# GANDHVEDH_Ammonia.net
KiCad netlist of a schematic drawn in Altium Designer
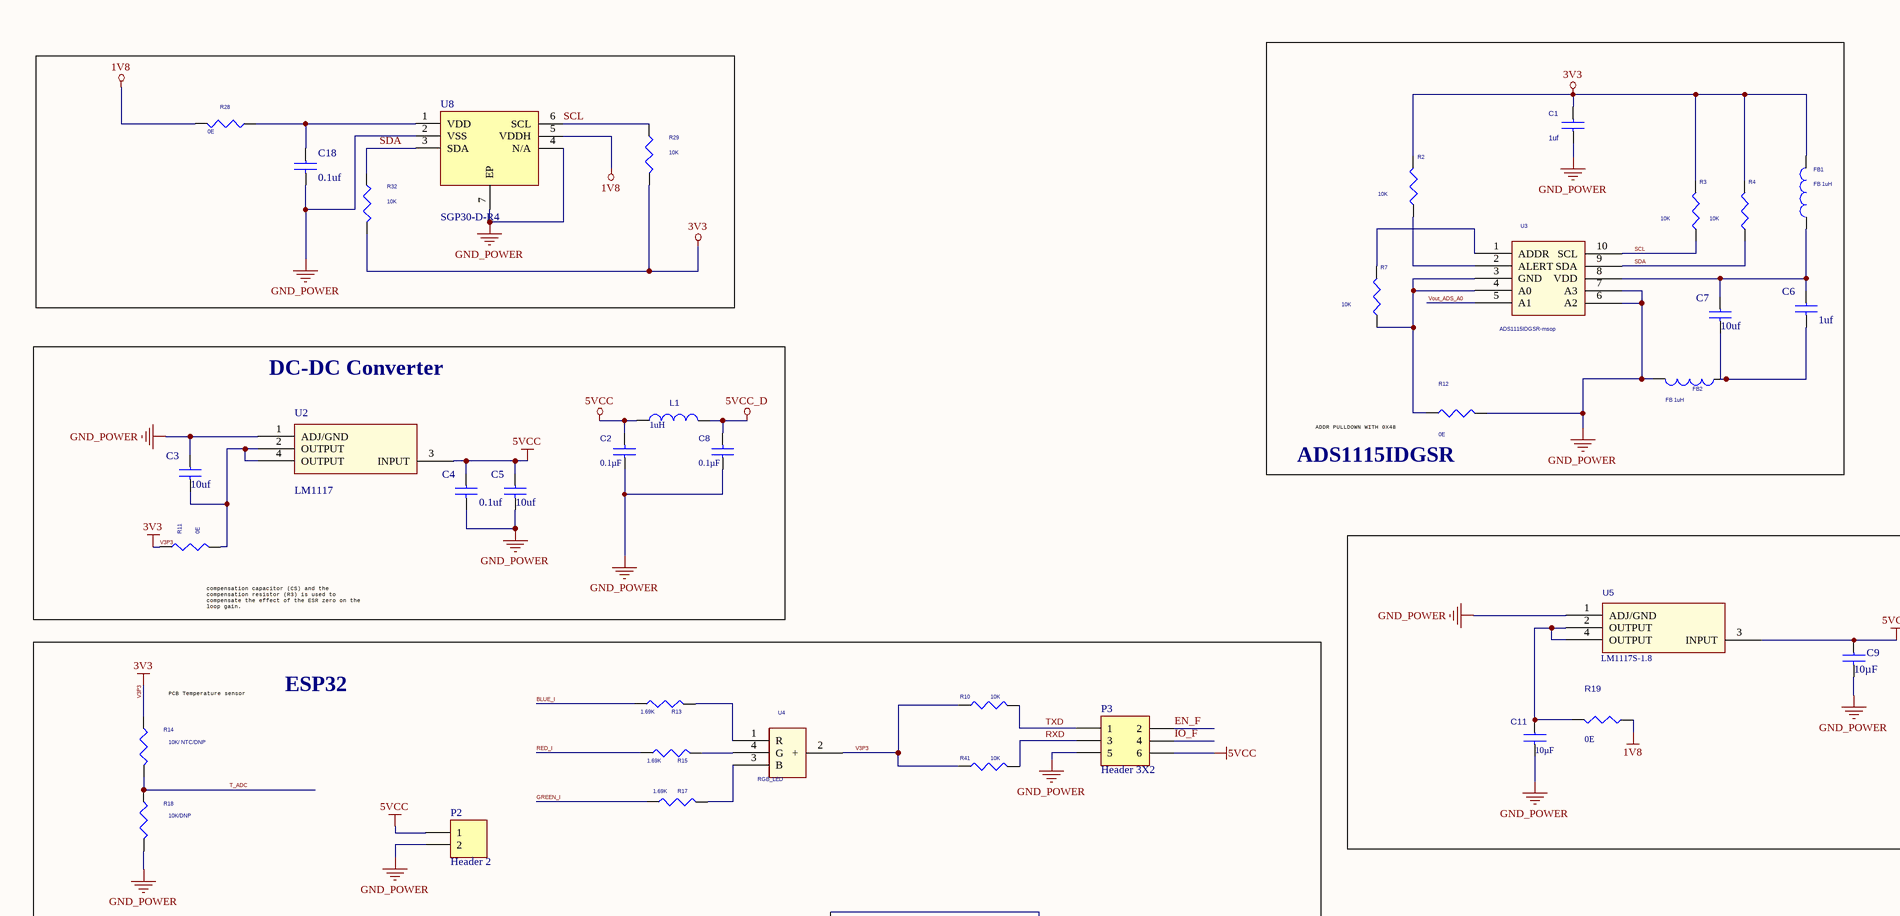
[diagram p0: GANDHVEDH_Ammonia.SchDoc, top left]
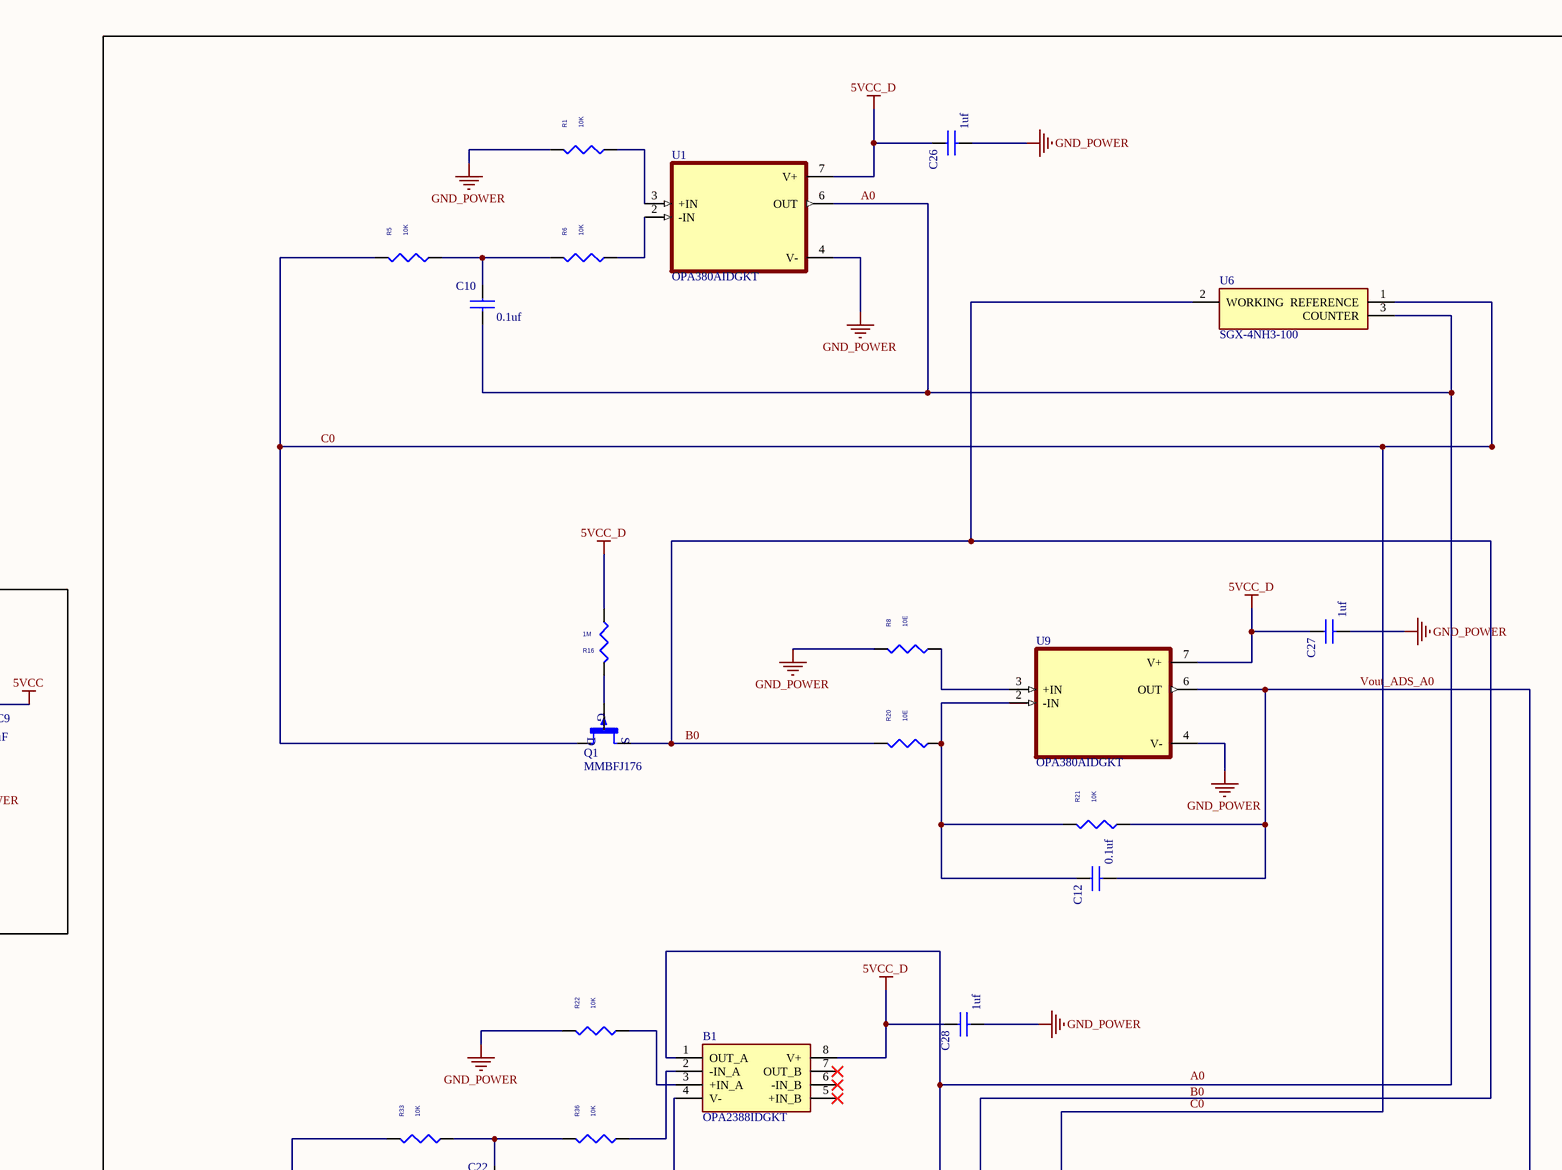
[diagram p1: GANDHVEDH_Ammonia.SchDoc, top right]
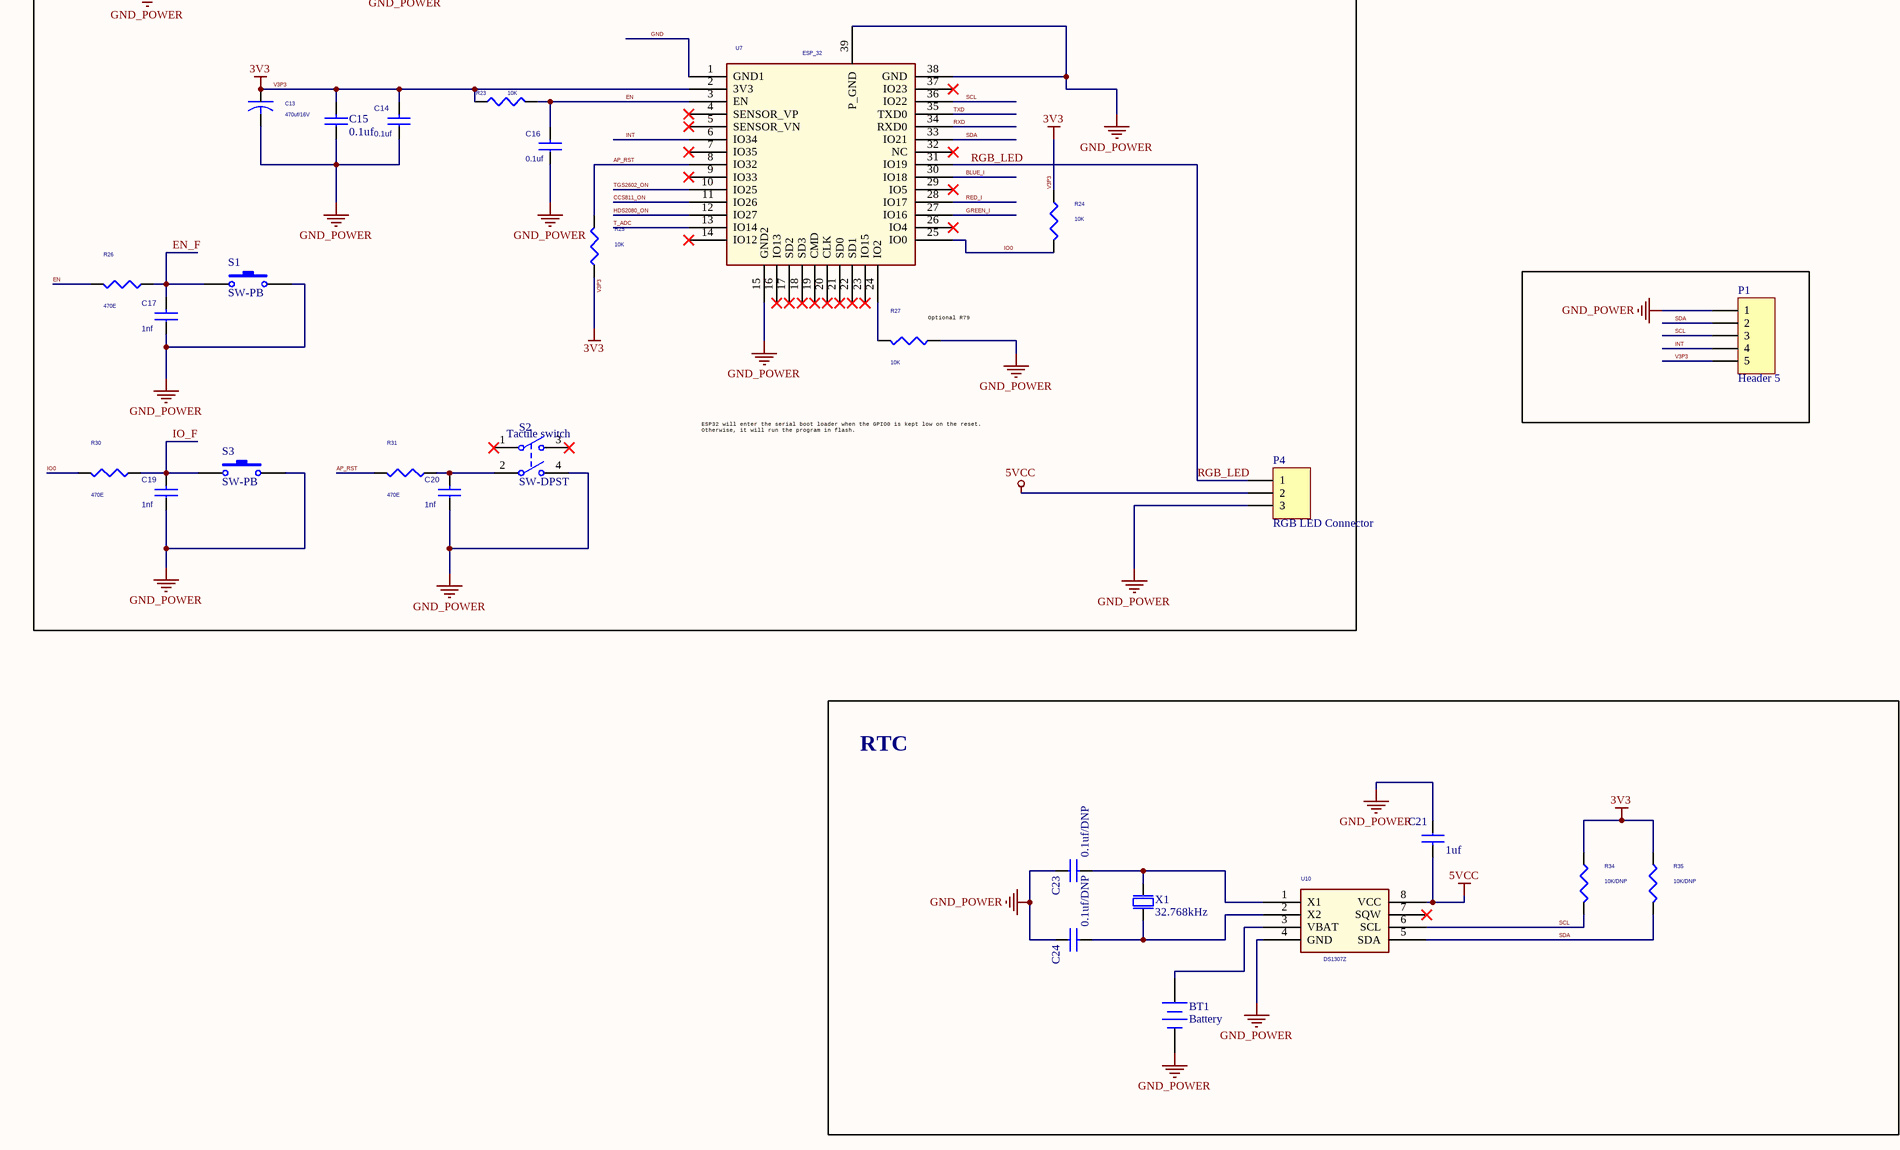
[diagram p2: GANDHVEDH_Ammonia.SchDoc, bottom left]
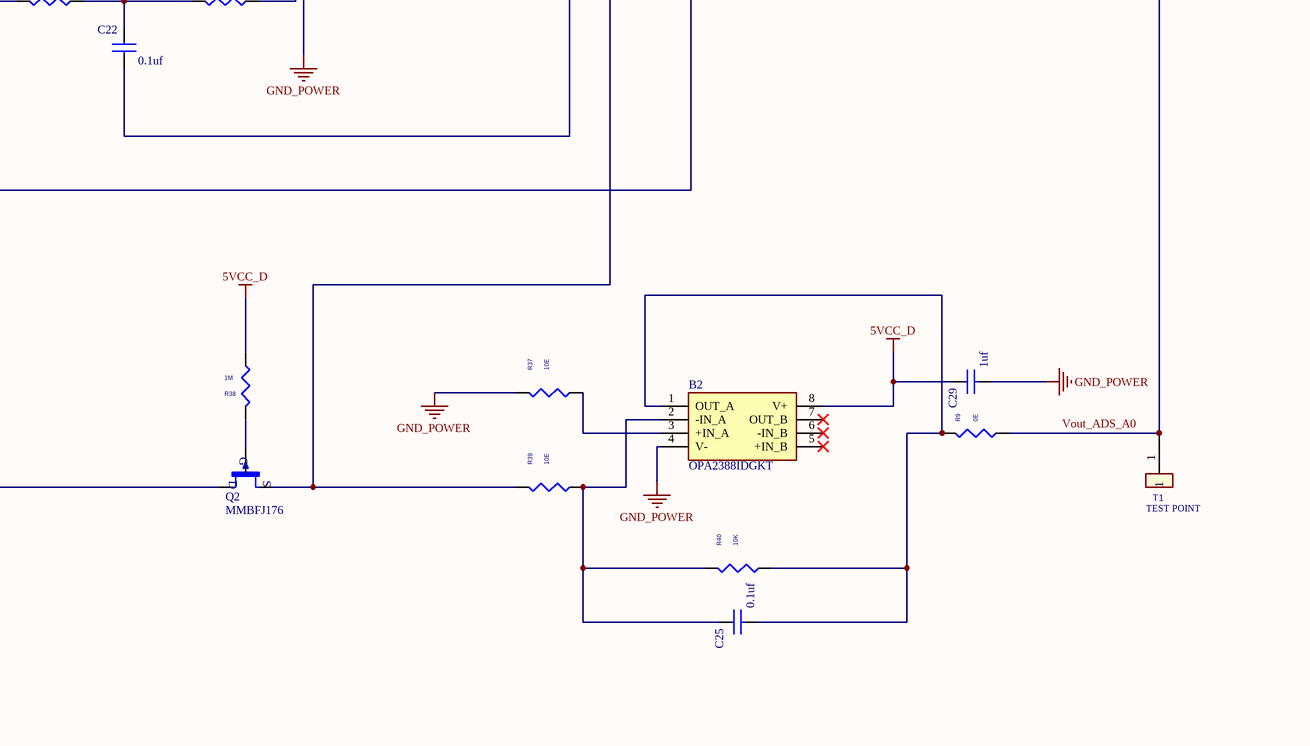
[diagram p3: GANDHVEDH_Ammonia.SchDoc, bottom right]

(export (version "E")
  (design (tool "Eeschema 10.0.6"))
  (components
    (comp (ref "B1")
      (value "OPA2388IDGKT")
      (footprint "SOP65P490X110-8N")
      (description "10MHz, CMOS, Zero-Drift, Zero-Crossover, True RRIO Precision Operational Amplifier")
      (fields (field (name "MOUSER PART NUMBER") "595-OPA2388IDGKT"))
      (libsource (lib "OPA2388IDGKT") (part "OPA2388IDGKT"))
    )
    (comp (ref "B2")
      (value "OPA2388IDGKT")
      (footprint "SOP65P490X110-8N")
      (description "10MHz, CMOS, Zero-Drift, Zero-Crossover, True RRIO Precision Operational Amplifier")
      (fields (field (name "MOUSER PART NUMBER") "595-OPA2388IDGKT"))
      (libsource (lib "OPA2388IDGKT") (part "OPA2388IDGKT"))
    )
    (comp (ref "BT1")
      (value "Battery")
      (footprint "Sensor Card:MPD_BK-912-TR")
      (description "Multicell Battery")
      (fields (field (name "PUBLISHER") "Altium Limited"))
      (libsource (lib "Miscellaneous Devices") (part "Battery"))
    )
    (comp (ref "C1")
      (value "1uf")
      (footprint "C0603")
      (description "CAP CER SMD 0.1µF/16V")
      (fields
        (field (name "MANUFACTURER") "Murata Electronics North America")
        (field (name "MANUFACTURER PART NUMBER") "GRM155R61H104KE19D")
      )
      (libsource (lib "Passive Component") (part "CAP_C_0.1µF/16V"))
    )
    (comp (ref "C2")
      (value "0.1µF")
      (footprint "C0603")
      (description "CAP CER SMD 0.1µF/16V")
      (fields
        (field (name "MANUFACTURER") "Murata Electronics North America")
        (field (name "MANUFACTURER PART NUMBER") "GRM155R61H104KE19D")
      )
      (libsource (lib "Passive Component") (part "CAP_C_0.1µF/16V"))
    )
    (comp (ref "C3")
      (value "10uf")
      (footprint "C0603")
      (description "CAP CER SMD 10µF/35V")
      (fields
        (field (name "MANUFACTURER") "Taiyo Yuden")
        (field (name "MANUFACTURER PART NUMBER") "GMK316AB7106KL-TR")
      )
      (libsource (lib "Passive Component") (part "CAP_C_10µF/35V"))
    )
    (comp (ref "C4")
      (value "0.1uf")
      (footprint "C0603")
      (description "CAP CER SMD 0.1µF/50V")
      (fields
        (field (name "MANUFACTURER") "Yageo")
        (field (name "MANUFACTURER PART NUMBER") "CC0805ZRY5V9BB104")
      )
      (libsource (lib "Passive Component") (part "CAP_C_0.1µF/50V"))
    )
    (comp (ref "C5")
      (value "10uf")
      (footprint "C0603")
      (description "CAP CER SMD 10µF/35V")
      (fields
        (field (name "MANUFACTURER") "Taiyo Yuden")
        (field (name "MANUFACTURER PART NUMBER") "GMK316AB7106KL-TR")
      )
      (libsource (lib "Passive Component") (part "CAP_C_10µF/35V"))
    )
    (comp (ref "C6")
      (value "1uf")
      (footprint "C0603")
      (description "CAP CER SMD 0.1µF/50V")
      (fields
        (field (name "MANUFACTURER") "Yageo")
        (field (name "MANUFACTURER PART NUMBER") "CC0805ZRY5V9BB104")
      )
      (libsource (lib "Passive Component") (part "CAP_C_0.1µF/50V"))
    )
    (comp (ref "C7")
      (value "10uf")
      (footprint "C0603")
      (description "CAP CER SMD 10µF/35V")
      (fields
        (field (name "MANUFACTURER") "Taiyo Yuden")
        (field (name "MANUFACTURER PART NUMBER") "GMK316AB7106KL-TR")
      )
      (libsource (lib "Passive Component") (part "CAP_C_10µF/35V"))
    )
    (comp (ref "C8")
      (value "0.1µF")
      (footprint "C0603")
      (description "CAP CER SMD 0.1µF/16V")
      (fields
        (field (name "MANUFACTURER") "Murata Electronics North America")
        (field (name "MANUFACTURER PART NUMBER") "GRM155R61H104KE19D")
      )
      (libsource (lib "Passive Component") (part "CAP_C_0.1µF/16V"))
    )
    (comp (ref "C9")
      (value "10µF")
      (footprint "R0603")
      (description "CAP CER SMD 10µF/35V")
      (fields
        (field (name "MANUFACTURER") "Taiyo Yuden")
        (field (name "MANUFACTURER PART NUMBER") "GMK316AB7106KL-TR")
      )
      (libsource (lib "Passive Component") (part "CAP_C_10µF/35V"))
    )
    (comp (ref "C10")
      (value "0.1uf")
      (footprint "C0603")
      (description "CAP CER SMD 0.1µF/50V")
      (fields
        (field (name "MANUFACTURER") "Yageo")
        (field (name "MANUFACTURER PART NUMBER") "CC0805ZRY5V9BB104")
      )
      (libsource (lib "Passive Component") (part "CAP_C_0.1µF/50V"))
    )
    (comp (ref "C11")
      (value "10µF")
      (footprint "C0603")
      (description "CAP CER SMD 10µF/35V")
      (fields
        (field (name "MANUFACTURER") "Taiyo Yuden")
        (field (name "MANUFACTURER PART NUMBER") "GMK316AB7106KL-TR")
      )
      (libsource (lib "Passive Component") (part "CAP_C_10µF/35V"))
    )
    (comp (ref "C12")
      (value "0.1uf")
      (footprint "C0603")
      (description "CAP CER SMD 0.1µF/50V")
      (fields
        (field (name "MANUFACTURER") "Yageo")
        (field (name "MANUFACTURER PART NUMBER") "CC0805ZRY5V9BB104")
      )
      (libsource (lib "Passive Component") (part "CAP_C_0.1µF/50V"))
    )
    (comp (ref "C13")
      (value "470uf/16V")
      (footprint "C16, C49, C58")
      (description "CAP ALUM 470UF 20% 50V RADIAL")
      (fields (field (name "PART NUMBER") "871-B41896E6477M000"))
      (libsource (lib "*") (part "CAP"))
    )
    (comp (ref "C14")
      (value "0.1uf")
      (footprint "C0603")
      (description "CAP CER SMD 0.1µF/16V")
      (fields
        (field (name "MANUFACTURER") "Murata Electronics North America")
        (field (name "MANUFACTURER PART NUMBER") "GRM155R61H104KE19D")
      )
      (libsource (lib "Passive Component") (part "CAP_C_0.1µF/16V"))
    )
    (comp (ref "C15")
      (value "0.1uf")
      (footprint "C0603")
      (description "CAP CER SMD 10µF/10V")
      (fields
        (field (name "MANUFACTURER") "Yageo")
        (field (name "MANUFACTURER PART NUMBER") "CC0805ZKY5V6BB106")
      )
      (libsource (lib "Passive Component") (part "CAP_C_10µF/10V"))
    )
    (comp (ref "C16")
      (value "0.1uf")
      (footprint "C0603")
      (description "CAP CER SMD 0.1µF/16V")
      (fields
        (field (name "MANUFACTURER") "Murata Electronics North America")
        (field (name "MANUFACTURER PART NUMBER") "GRM155R61H104KE19D")
      )
      (libsource (lib "Passive Component") (part "CAP_C_0.1µF/16V"))
    )
    (comp (ref "C17")
      (value "1nf")
      (footprint "C0603")
      (description "CAP CER SMD 0.1µF/16V")
      (fields
        (field (name "MANUFACTURER") "Murata Electronics North America")
        (field (name "MANUFACTURER PART NUMBER") "GRM155R61H104KE19D")
      )
      (libsource (lib "Passive Component") (part "CAP_C_0.1µF/16V"))
    )
    (comp (ref "C18")
      (value "0.1uf")
      (footprint "C0603")
      (description "CAP CER SMD 0.1µF/50V")
      (fields
        (field (name "MANUFACTURER") "Yageo")
        (field (name "MANUFACTURER PART NUMBER") "CC0805ZRY5V9BB104")
      )
      (libsource (lib "Passive Component") (part "CAP_C_0.1µF/50V"))
    )
    (comp (ref "C19")
      (value "1nf")
      (footprint "C0603")
      (description "CAP CER SMD 0.1µF/16V")
      (fields
        (field (name "MANUFACTURER") "Murata Electronics North America")
        (field (name "MANUFACTURER PART NUMBER") "GRM155R61H104KE19D")
      )
      (libsource (lib "Passive Component") (part "CAP_C_0.1µF/16V"))
    )
    (comp (ref "C20")
      (value "1nf")
      (footprint "C0603")
      (description "CAP CER SMD 0.1µF/16V")
      (fields
        (field (name "MANUFACTURER") "Murata Electronics North America")
        (field (name "MANUFACTURER PART NUMBER") "GRM155R61H104KE19D")
      )
      (libsource (lib "Passive Component") (part "CAP_C_0.1µF/16V"))
    )
    (comp (ref "C21")
      (value "1uf")
      (footprint "C0603")
      (description "CAP CER SMD 0.1µF/50V")
      (fields
        (field (name "MANUFACTURER") "Yageo")
        (field (name "MANUFACTURER PART NUMBER") "CC0805ZRY5V9BB104")
      )
      (libsource (lib "Passive Component") (part "CAP_C_0.1µF/50V"))
    )
    (comp (ref "C22")
      (value "0.1uf")
      (footprint "C0603")
      (description "CAP CER SMD 0.1µF/50V")
      (fields
        (field (name "MANUFACTURER") "Yageo")
        (field (name "MANUFACTURER PART NUMBER") "CC0805ZRY5V9BB104")
      )
      (libsource (lib "Passive Component") (part "CAP_C_0.1µF/50V"))
    )
    (comp (ref "C23")
      (value "0.1uf/DNP")
      (footprint "C0603")
      (description "CAP CER SMD 0.1µF/50V")
      (fields
        (field (name "MANUFACTURER") "Yageo")
        (field (name "MANUFACTURER PART NUMBER") "CC0805ZRY5V9BB104")
      )
      (libsource (lib "Passive Component") (part "CAP_C_0.1µF/50V"))
    )
    (comp (ref "C24")
      (value "0.1uf/DNP")
      (footprint "C0603")
      (description "CAP CER SMD 0.1µF/50V")
      (fields
        (field (name "MANUFACTURER") "Yageo")
        (field (name "MANUFACTURER PART NUMBER") "CC0805ZRY5V9BB104")
      )
      (libsource (lib "Passive Component") (part "CAP_C_0.1µF/50V"))
    )
    (comp (ref "C25")
      (value "0.1uf")
      (footprint "C0603")
      (description "CAP CER SMD 0.1µF/50V")
      (fields
        (field (name "MANUFACTURER") "Yageo")
        (field (name "MANUFACTURER PART NUMBER") "CC0805ZRY5V9BB104")
      )
      (libsource (lib "Passive Component") (part "CAP_C_0.1µF/50V"))
    )
    (comp (ref "C26")
      (value "1uf")
      (footprint "C0603")
      (description "CAP CER SMD 0.1µF/50V")
      (fields
        (field (name "MANUFACTURER") "Yageo")
        (field (name "MANUFACTURER PART NUMBER") "CC0805ZRY5V9BB104")
      )
      (libsource (lib "Passive Component") (part "CAP_C_0.1µF/50V"))
    )
    (comp (ref "C27")
      (value "1uf")
      (footprint "C0603")
      (description "CAP CER SMD 0.1µF/50V")
      (fields
        (field (name "MANUFACTURER") "Yageo")
        (field (name "MANUFACTURER PART NUMBER") "CC0805ZRY5V9BB104")
      )
      (libsource (lib "Passive Component") (part "CAP_C_0.1µF/50V"))
    )
    (comp (ref "C28")
      (value "1uf")
      (footprint "C0603")
      (description "CAP CER SMD 0.1µF/50V")
      (fields
        (field (name "MANUFACTURER") "Yageo")
        (field (name "MANUFACTURER PART NUMBER") "CC0805ZRY5V9BB104")
      )
      (libsource (lib "Passive Component") (part "CAP_C_0.1µF/50V"))
    )
    (comp (ref "C29")
      (value "1uf")
      (footprint "C0603")
      (description "CAP CER SMD 0.1µF/50V")
      (fields
        (field (name "MANUFACTURER") "Yageo")
        (field (name "MANUFACTURER PART NUMBER") "CC0805ZRY5V9BB104")
      )
      (libsource (lib "Passive Component") (part "CAP_C_0.1µF/50V"))
    )
    (comp (ref "FB1")
      (value "FB 1uH")
      (footprint "C0603")
      (description "FILTER CHIP 120 OHM 3A 0603")
      (fields (field (name "MANUFACTURER PART NUMBER") "MMZ2012Y152B"))
      (libsource (lib "*") (part "INDUCTOR"))
    )
    (comp (ref "FB2")
      (value "FB 1uH")
      (footprint "C0603")
      (description "FILTER CHIP 120 OHM 3A 0603")
      (fields (field (name "DISTRIBUTOR PART NUMBER") "MMZ2012Y152B"))
      (libsource (lib "*") (part "INDUCTOR"))
    )
    (comp (ref "L1")
      (value "1uH")
      (footprint "L3, L4, L5, L6, L7")
      (description "FERRITE BEAD 120 OHM 0603 1LN")
      (fields (field (name "PART NUMBER") "490-3996-1-ND"))
      (libsource (lib "*") (part "INDUCTOR"))
    )
    (comp (ref "P1")
      (value "Header 5")
      (footprint "J2")
      (description "Header, 5-Pin")
      (fields (field (name "PUBLISHER") "Altium Limited"))
      (libsource (lib "Miscellaneous Connectors") (part "Header 5"))
    )
    (comp (ref "P2")
      (value "Header 2")
      (footprint "Miscellaneous Connectors:HDR1X2")
      (description "Header, 2-Pin")
      (fields (field (name "PUBLISHER") "Altium Limited"))
      (libsource (lib "Miscellaneous Connectors") (part "Header 2"))
    )
    (comp (ref "P3")
      (value "Header 3X2")
      (footprint "P5 - new")
      (description "Header, 3-Pin, Dual row")
      (fields (field (name "PUBLISHER") "Altium Limited"))
      (libsource (lib "Miscellaneous Connectors") (part "Header 3X2"))
    )
    (comp (ref "P4")
      (value "RGB LED Connector")
      (footprint "P6")
      (description "Header, 3-Pin")
      (fields (field (name "PUBLISHER") "Altium Limited"))
      (libsource (lib "Miscellaneous Connectors") (part "Header 3"))
    )
    (comp (ref "Q1")
      (value "MMBFJ176")
      (footprint "SOT23")
      (description "JFET P-Channel 30V 225mW Surface Mount SOT-23-3")
      (fields (field (name "MF") "ON Semiconductor"))
      (libsource (lib "MMBFJ176") (part "MMBFJ176"))
    )
    (comp (ref "Q2")
      (value "MMBFJ176")
      (footprint "SOT23")
      (description "JFET P-Channel 30V 225mW Surface Mount SOT-23-3")
      (fields (field (name "MF") "ON Semiconductor"))
      (libsource (lib "MMBFJ176") (part "MMBFJ176"))
    )
    (comp (ref "R1") (value "10K") (footprint "R0603") (libsource (lib "*") (part "R")))
    (comp (ref "R2")
      (value "10K")
      (footprint "R0603")
      (description "RES SMD 4.7K OHM 1% 1/16W 0603")
      (fields (field (name "TOLERANCE") "1%") (field (name "DISTRIBUTOR PART NUMBER") "1276-3466-2-ND"))
      (libsource (lib "*") (part "R"))
    )
    (comp (ref "R3")
      (value "10K")
      (footprint "R0603")
      (description "RES SMD 4.7K OHM 1% 1/16W 0603")
      (fields (field (name "TOLERANCE") "1%") (field (name "DISTRIBUTOR PART NUMBER") "1276-3466-2-ND"))
      (libsource (lib "*") (part "R"))
    )
    (comp (ref "R4")
      (value "10K")
      (footprint "R0603")
      (description "RES SMD 4.7K OHM 1% 1/16W 0603")
      (fields (field (name "TOLERANCE") "1%") (field (name "DISTRIBUTOR PART NUMBER") "1276-3466-2-ND"))
      (libsource (lib "*") (part "R"))
    )
    (comp (ref "R5") (value "10K") (footprint "R0603") (libsource (lib "*") (part "R")))
    (comp (ref "R6") (value "10K") (footprint "R0603") (libsource (lib "*") (part "R")))
    (comp (ref "R7")
      (value "10K")
      (footprint "R0603")
      (description "RES SMD 4.7K OHM 1% 1/16W 0603")
      (fields (field (name "TOLERANCE") "1%") (field (name "DISTRIBUTOR PART NUMBER") "1276-3466-2-ND"))
      (libsource (lib "*") (part "R"))
    )
    (comp (ref "R8") (value "10E") (footprint "R0603") (libsource (lib "*") (part "R")))
    (comp (ref "R9") (value "0E") (footprint "R0603") (libsource (lib "*") (part "R")))
    (comp (ref "R10")
      (value "10K")
      (footprint "R_0603_W")
      (description "RES SMD 4.7K OHM 1% 1/16W 0603")
      (fields (field (name "PART NUMBER") "311-10KGRTR-ND"))
      (libsource (lib "*") (part "R"))
    )
    (comp (ref "R11")
      (value "0E")
      (footprint "R0603")
      (description "RES SMD 40.2K OHM 0.1% 1/5W 0603")
      (fields (field (name "PART NUMBER") "P20154TR-ND"))
      (libsource (lib "*") (part "R"))
    )
    (comp (ref "R12") (value "0E") (footprint "R0603") (libsource (lib "*") (part "R")))
    (comp (ref "R13")
      (value "1.69K")
      (footprint "R0603")
      (description "RES SMD 4.7K OHM 1% 1/16W 0603")
      (fields (field (name "PART NUMBER") "311-10KGRTR-ND"))
      (libsource (lib "*") (part "R"))
    )
    (comp (ref "R14")
      (value "10K/ NTC/DNP")
      (footprint "R0603")
      (description "THERMISTOR NTC 10KOHM 3380K 0603")
      (fields (field (name "PART NUMBER") "490-16279-2-ND"))
      (libsource (lib "*") (part "R"))
    )
    (comp (ref "R15")
      (value "1.69K")
      (footprint "R0603")
      (description "RES SMD 4.7K OHM 1% 1/16W 0603")
      (fields (field (name "PART NUMBER") "311-10KGRTR-ND"))
      (libsource (lib "*") (part "R"))
    )
    (comp (ref "R16") (value "1M") (footprint "R0603") (libsource (lib "*") (part "R")))
    (comp (ref "R17")
      (value "1.69K")
      (footprint "R0603")
      (description "RES SMD 4.7K OHM 1% 1/16W 0603")
      (fields (field (name "PART NUMBER") "311-10KGRTR-ND"))
      (libsource (lib "*") (part "R"))
    )
    (comp (ref "R18")
      (value "10K/DNP")
      (footprint "R0603")
      (description "RES SMD 4.7K OHM 1% 1/16W 0603")
      (fields (field (name "PART NUMBER") "311-10KGRTR-ND"))
      (libsource (lib "*") (part "R"))
    )
    (comp (ref "R19")
      (value "0E")
      (footprint "R0603")
      (description "RES SMD 470 OHM 1% 1/10W 0603")
      (fields (field (name "PART NUMBER") "311-470HRCT-ND"))
      (libsource (lib "*") (part "R"))
    )
    (comp (ref "R20") (value "10E") (footprint "R0603") (libsource (lib "*") (part "R")))
    (comp (ref "R21") (value "10K") (footprint "R0603") (libsource (lib "*") (part "R")))
    (comp (ref "R22") (value "10K") (footprint "R0603") (libsource (lib "*") (part "R")))
    (comp (ref "R23")
      (value "10K")
      (footprint "R0603")
      (description "RES SMD 4.7K OHM 1% 1/16W 0603")
      (fields (field (name "PART NUMBER") "311-10KGRTR-ND"))
      (libsource (lib "*") (part "R"))
    )
    (comp (ref "R24")
      (value "10K")
      (footprint "R0603")
      (description "RES SMD 4.7K OHM 1% 1/16W 0603")
      (fields (field (name "PART NUMBER") "311-10KGRTR-ND"))
      (libsource (lib "*") (part "R"))
    )
    (comp (ref "R25")
      (value "10K")
      (footprint "R0603")
      (description "RES SMD 4.7K OHM 1% 1/16W 0603")
      (fields (field (name "PART NUMBER") "311-10KGRTR-ND"))
      (libsource (lib "*") (part "R"))
    )
    (comp (ref "R26")
      (value "470E")
      (footprint "R0603")
      (description "RES SMD 470 OHM 1% 1/10W 0603")
      (fields (field (name "PART NUMBER") "311-470HRCT-ND"))
      (libsource (lib "*") (part "R"))
    )
    (comp (ref "R27")
      (value "10K")
      (footprint "R0603")
      (description "RES SMD 4.7K OHM 1% 1/16W 0603")
      (fields (field (name "PART NUMBER") "311-10KGRTR-ND"))
      (libsource (lib "*") (part "R"))
    )
    (comp (ref "R28")
      (value "0E")
      (footprint "R0603")
      (description "RES SMD 4.7K OHM 1% 1/16W 0603")
      (fields (field (name "PART NUMBER") "311-10KGRTR-ND"))
      (libsource (lib "*") (part "R"))
    )
    (comp (ref "R29")
      (value "10K")
      (footprint "R0603")
      (description "RES SMD 4.7K OHM 1% 1/16W 0603")
      (fields (field (name "PART NUMBER") "311-10KGRTR-ND"))
      (libsource (lib "*") (part "R"))
    )
    (comp (ref "R30")
      (value "470E")
      (footprint "R0603")
      (description "RES SMD 470 OHM 1% 1/10W 0603")
      (fields (field (name "PART NUMBER") "311-470HRCT-ND"))
      (libsource (lib "*") (part "R"))
    )
    (comp (ref "R31")
      (value "470E")
      (footprint "R0603")
      (description "RES SMD 470 OHM 1% 1/10W 0603")
      (fields (field (name "PART NUMBER") "311-470HRCT-ND"))
      (libsource (lib "*") (part "R"))
    )
    (comp (ref "R32")
      (value "10K")
      (footprint "R0603")
      (description "RES SMD 4.7K OHM 1% 1/16W 0603")
      (fields (field (name "PART NUMBER") "311-10KGRTR-ND"))
      (libsource (lib "*") (part "R"))
    )
    (comp (ref "R33") (value "10K") (footprint "R0603") (libsource (lib "*") (part "R")))
    (comp (ref "R34")
      (value "10K/DNP")
      (footprint "R0603")
      (description "RES SMD 4.7K OHM 1% 1/16W 0603")
      (fields (field (name "PART NUMBER") "311-10KGRTR-ND"))
      (libsource (lib "*") (part "R"))
    )
    (comp (ref "R35")
      (value "10K/DNP")
      (footprint "R0603")
      (description "RES SMD 4.7K OHM 1% 1/16W 0603")
      (fields (field (name "PART NUMBER") "311-10KGRTR-ND"))
      (libsource (lib "*") (part "R"))
    )
    (comp (ref "R36") (value "10K") (footprint "R0603") (libsource (lib "*") (part "R")))
    (comp (ref "R37") (value "10E") (footprint "R0603") (libsource (lib "*") (part "R")))
    (comp (ref "R38") (value "1M") (footprint "R0603") (libsource (lib "*") (part "R")))
    (comp (ref "R39") (value "10E") (footprint "R0603") (libsource (lib "*") (part "R")))
    (comp (ref "R40") (value "10K") (footprint "R0603") (libsource (lib "*") (part "R")))
    (comp (ref "R41")
      (value "10K")
      (footprint "R_0603_W")
      (description "RES SMD 4.7K OHM 1% 1/16W 0603")
      (fields (field (name "PART NUMBER") "311-10KGRTR-ND"))
      (libsource (lib "*") (part "R"))
    )
    (comp (ref "S1")
      (value "SW-PB")
      (footprint "*TE_FSMSM")
      (description "Switch")
      (fields (field (name "PUBLISHER") "Altium Limited"))
      (libsource (lib "Miscellaneous Devices") (part "SW-PB"))
    )
    (comp (ref "S2")
      (value "SW-DPST")
      (footprint "PCBComponent_1 - duplicate")
      (description "Double-Pole, Single-Throw Switch")
      (fields (field (name "PUBLISHER") "Altium Limited"))
      (libsource (lib "Miscellaneous Devices") (part "SW-DPST"))
    )
    (comp (ref "S3")
      (value "SW-PB")
      (footprint "*TE_FSMSM")
      (description "Switch")
      (fields (field (name "PUBLISHER") "Altium Limited"))
      (libsource (lib "Miscellaneous Devices") (part "SW-PB"))
    )
    (comp (ref "T1") (value "TEST POINT") (footprint "TP") (libsource (lib "*") (part "Test_P")))
    (comp (ref "U1")
      (value "OPA380AIDGKT")
      (footprint "SOP65P490X110-8N")
      (libsource (lib "OPA380AIDGKT") (part "OPA380AIDGKT"))
    )
    (comp (ref "U2")
      (value "LM1117")
      (footprint "U1, U24              SOT-223")
      (description "3.3V LDO")
      (fields (field (name "MANUFACTURER") "Texas Instruments"))
      (libsource (lib "PMIC") (part "TLV70033DDCT"))
    )
    (comp (ref "U3")
      (value "ADS1115IDGSR-msop")
      (footprint "U19, U20")
      (description "IC ADC 16BIT SIGMA-DELTA 10VSSOP")
      (fields (field (name "PART NUMBER") "595-ADS1115IDGST"))
      (libsource (lib "*") (part "ADS1115"))
    )
    (comp (ref "U4")
      (value "RGB_LED")
      (footprint "Sensor Card:WL-SFCW_1206")
      (fields (field (name "PART NUMBER") "754-1492-ND"))
      (libsource (lib "*") (part "RGB_LED_PTH_0"))
    )
    (comp (ref "U5")
      (value "LM1117S-1.8")
      (footprint "U1, U24              SOT-223")
      (description "3.3V LDO")
      (fields
        (field (name "MANUFACTURER") "Texas Instruments")
        (field (name "MANUFACTURER PART NUMBER") "LM1117")
      )
      (libsource (lib "PMIC") (part "TLV70033DDCT"))
    )
    (comp (ref "U6")
      (value "SGX-4NH3-100")
      (footprint "SGX4NH3100")
      (description "Air Quality Sensors 4 Series Ammonia sensor - 100ppm")
      (fields (field (name "MOUSER PART NUMBER") "523-SGX-4NH3-100"))
      (libsource (lib "SGX-4NH3-100") (part "SGX-4NH3-100"))
    )
    (comp (ref "U7")
      (value "ESP_32")
      (footprint "U20             ESP 32")
      (description "WIFI MODULE 128MBITS SPI FLASH")
      (fields (field (name "PART NUMBER") "356-ES32WROOM32D16MB"))
      (libsource (lib "*") (part "ESP32_SMD_1"))
    )
    (comp (ref "U8")
      (value "SGP30-D-R4")
      (footprint "SGP40-D-R4 (1):XCDR_SGP40-D-R4")
      (description "Integrated Circuit")
      (fields
        (field (name "MANUFACTURER_PART_NUMBER") "SGP40-D-R4")
        (field (name "MOUSER PART NUMBER") "403-SGP40-D-R4")
      )
      (libsource (lib "*") (part "SGP40-D-R4"))
    )
    (comp (ref "U9")
      (value "OPA380AIDGKT")
      (footprint "SOP65P490X110-8N")
      (libsource (lib "OPA380AIDGKT") (part "OPA380AIDGKT"))
    )
    (comp (ref "U10")
      (value "DS1307Z")
      (footprint "U14               SOIC-8N")
      (description "IC REG BUCK ADJUSTABLE 3A 8SOIC")
      (fields (field (name "PART NUMBER") "1589-1533-1-ND"))
      (libsource (lib "*") (part "MP1584_SOIC_0"))
    )
    (comp (ref "X1")
      (value "32.768kHz")
      (footprint "XTAL_ECS-.327-12.5-13FLX-C")
      (description "XTAL SMD 3215, 32.768kHz, Cl=9pF, Total Tol: ±50ppm")
      (fields
        (field (name "PART NUMBER") "XTAL_SMD3215_32.768kHz_9pF_General")
        (field (name "PUBLISHER") "Nordic Semiconductor")
      )
      (libsource (lib "Sensor Card") (part "XTAL_2-pin"))
    )
  )
  (nets
    (net (code "1") (name "/A0") (class "Default")
      (node (ref "B1") (pin "1") (pinfunction "OUT_A_1") (pintype "passive"))
      (node (ref "C10") (pin "2") (pinfunction "2_2") (pintype "passive"))
      (node (ref "C22") (pin "2") (pinfunction "2_2") (pintype "passive"))
      (node (ref "U1") (pin "6") (pinfunction "OUT_6") (pintype "output"))
      (node (ref "U6") (pin "3") (pinfunction "COUNTER_3") (pintype "passive"))
    )
    (net (code "2") (name "/AP_RST") (class "Default")
      (node (ref "R25") (pin "2") (pinfunction "2_2") (pintype "passive"))
      (node (ref "R31") (pin "2") (pinfunction "2_2") (pintype "passive"))
      (node (ref "U7") (pin "8") (pinfunction "IO32_8") (pintype "passive"))
    )
    (net (code "3") (name "/B0") (class "Default")
      (node (ref "Q1") (pin "2") (pinfunction "S_2") (pintype "passive"))
      (node (ref "Q2") (pin "2") (pinfunction "S_2") (pintype "passive"))
      (node (ref "R20") (pin "2") (pinfunction "2_2") (pintype "passive"))
      (node (ref "R39") (pin "2") (pinfunction "2_2") (pintype "passive"))
      (node (ref "U6") (pin "2") (pinfunction "WORKING_2") (pintype "passive"))
    )
    (net (code "4") (name "/BLUE_I") (class "Default")
      (node (ref "R13") (pin "1") (pinfunction "1_1") (pintype "passive"))
      (node (ref "U7") (pin "30") (pinfunction "IO18_30") (pintype "passive"))
    )
    (net (code "5") (name "/C0") (class "Default")
      (node (ref "Q1") (pin "1") (pinfunction "D_1") (pintype "passive"))
      (node (ref "Q2") (pin "1") (pinfunction "D_1") (pintype "passive"))
      (node (ref "R33") (pin "2") (pinfunction "2_2") (pintype "passive"))
      (node (ref "R5") (pin "2") (pinfunction "2_2") (pintype "passive"))
      (node (ref "U6") (pin "1") (pinfunction "REFERENCE_1") (pintype "passive"))
    )
    (net (code "6") (name "/CCS811_ON") (class "Default")
      (node (ref "U7") (pin "11") (pinfunction "IO26_11") (pintype "passive"))
    )
    (net (code "7") (name "/EN") (class "Default")
      (node (ref "C16") (pin "2") (pinfunction "2_2") (pintype "passive"))
      (node (ref "R23") (pin "2") (pinfunction "2_2") (pintype "passive"))
      (node (ref "R26") (pin "2") (pinfunction "2_2") (pintype "passive"))
      (node (ref "U7") (pin "3") (pinfunction "EN_3") (pintype "passive"))
    )
    (net (code "8") (name "/EN_F") (class "Default")
      (node (ref "C17") (pin "2") (pinfunction "2_2") (pintype "passive"))
      (node (ref "P3") (pin "2") (pinfunction "2_2") (pintype "passive"))
      (node (ref "R26") (pin "1") (pinfunction "1_1") (pintype "passive"))
      (node (ref "S1") (pin "1") (pinfunction "1_1") (pintype "passive"))
    )
    (net (code "9") (name "/GND") (class "Default")
      (node (ref "U7") (pin "1") (pinfunction "GND1_1") (pintype "passive"))
    )
    (net (code "10") (name "/GREEN_I") (class "Default")
      (node (ref "R17") (pin "1") (pinfunction "1_1") (pintype "passive"))
      (node (ref "U7") (pin "27") (pinfunction "IO16_27") (pintype "passive"))
    )
    (net (code "11") (name "/HDS2080_ON") (class "Default")
      (node (ref "U7") (pin "12") (pinfunction "IO27_12") (pintype "passive"))
    )
    (net (code "12") (name "/INT") (class "Default")
      (node (ref "P1") (pin "4") (pinfunction "4_4") (pintype "passive"))
      (node (ref "U7") (pin "6") (pinfunction "IO34_6") (pintype "passive"))
    )
    (net (code "13") (name "/IO0") (class "Default")
      (node (ref "R24") (pin "2") (pinfunction "2_2") (pintype "passive"))
      (node (ref "R30") (pin "2") (pinfunction "2_2") (pintype "passive"))
      (node (ref "U7") (pin "25") (pinfunction "IO0_25") (pintype "passive"))
    )
    (net (code "14") (name "/IO_F") (class "Default")
      (node (ref "C19") (pin "2") (pinfunction "2_2") (pintype "passive"))
      (node (ref "P3") (pin "4") (pinfunction "4_4") (pintype "passive"))
      (node (ref "R30") (pin "1") (pinfunction "1_1") (pintype "passive"))
      (node (ref "S3") (pin "1") (pinfunction "1_1") (pintype "passive"))
    )
    (net (code "15") (name "/RED_I") (class "Default")
      (node (ref "R15") (pin "1") (pinfunction "1_1") (pintype "passive"))
      (node (ref "U7") (pin "28") (pinfunction "IO17_28") (pintype "passive"))
    )
    (net (code "16") (name "/RGB_LED") (class "Default")
      (node (ref "P4") (pin "1") (pinfunction "1_1") (pintype "passive"))
      (node (ref "U7") (pin "31") (pinfunction "IO19_31") (pintype "passive"))
    )
    (net (code "17") (name "/RXD") (class "Default")
      (node (ref "P3") (pin "3") (pinfunction "3_3") (pintype "passive"))
      (node (ref "R41") (pin "2") (pinfunction "2_2") (pintype "passive"))
      (node (ref "U7") (pin "34") (pinfunction "RXD0_34") (pintype "passive"))
    )
    (net (code "18") (name "/SCL") (class "Default")
      (node (ref "P1") (pin "3") (pinfunction "3_3") (pintype "passive"))
      (node (ref "R29") (pin "1") (pinfunction "1_1") (pintype "passive"))
      (node (ref "R3") (pin "2") (pinfunction "2_2") (pintype "passive"))
      (node (ref "R34") (pin "2") (pinfunction "2_2") (pintype "passive"))
      (node (ref "U10") (pin "6") (pinfunction "SCL_6") (pintype "passive"))
      (node (ref "U3") (pin "10") (pinfunction "SCL_10") (pintype "passive"))
      (node (ref "U7") (pin "36") (pinfunction "IO22_36") (pintype "passive"))
      (node (ref "U8") (pin "6") (pinfunction "SCL_6") (pintype "passive"))
    )
    (net (code "19") (name "/SDA") (class "Default")
      (node (ref "P1") (pin "2") (pinfunction "2_2") (pintype "passive"))
      (node (ref "R32") (pin "1") (pinfunction "1_1") (pintype "passive"))
      (node (ref "R35") (pin "2") (pinfunction "2_2") (pintype "passive"))
      (node (ref "R4") (pin "2") (pinfunction "2_2") (pintype "passive"))
      (node (ref "U10") (pin "5") (pinfunction "SDA_5") (pintype "passive"))
      (node (ref "U3") (pin "9") (pinfunction "SDA_9") (pintype "passive"))
      (node (ref "U7") (pin "33") (pinfunction "IO21_33") (pintype "passive"))
      (node (ref "U8") (pin "3") (pinfunction "SDA_3") (pintype "passive"))
    )
    (net (code "20") (name "/TGS2602_ON") (class "Default")
      (node (ref "U7") (pin "10") (pinfunction "IO25_10") (pintype "passive"))
    )
    (net (code "21") (name "/TXD") (class "Default")
      (node (ref "P3") (pin "1") (pinfunction "1_1") (pintype "passive"))
      (node (ref "R10") (pin "2") (pinfunction "2_2") (pintype "passive"))
      (node (ref "U7") (pin "35") (pinfunction "TXD0_35") (pintype "passive"))
    )
    (net (code "22") (name "/T_ADC") (class "Default")
      (node (ref "R14") (pin "2") (pinfunction "2_2") (pintype "passive"))
      (node (ref "R18") (pin "1") (pinfunction "1_1") (pintype "passive"))
      (node (ref "U7") (pin "13") (pinfunction "IO14_13") (pintype "passive"))
    )
    (net (code "23") (name "/Vout_ADS_A0") (class "Default")
      (node (ref "C12") (pin "2") (pinfunction "2_2") (pintype "passive"))
      (node (ref "R21") (pin "1") (pinfunction "1_1") (pintype "passive"))
      (node (ref "R9") (pin "1") (pinfunction "1_1") (pintype "passive"))
      (node (ref "T1") (pin "1") (pinfunction "1_1") (pintype "passive"))
      (node (ref "U3") (pin "5") (pinfunction "A1_5") (pintype "passive"))
      (node (ref "U9") (pin "6") (pinfunction "OUT_6") (pintype "output"))
    )
    (net (code "24") (name "1V8") (class "Default")
      (node (ref "R19") (pin "1") (pinfunction "1_1") (pintype "passive"))
      (node (ref "R28") (pin "2") (pinfunction "2_2") (pintype "passive"))
      (node (ref "U8") (pin "5") (pinfunction "VDDH_5") (pintype "passive"))
    )
    (net (code "25") (name "3V3") (class "Default")
      (node (ref "C1") (pin "2") (pinfunction "2_2") (pintype "passive"))
      (node (ref "C13") (pin "1") (pinfunction "1_1") (pintype "passive"))
      (node (ref "C14") (pin "2") (pinfunction "2_2") (pintype "passive"))
      (node (ref "C15") (pin "2") (pinfunction "2_2") (pintype "passive"))
      (node (ref "FB1") (pin "2") (pinfunction "2_2") (pintype "passive"))
      (node (ref "P1") (pin "5") (pinfunction "5_5") (pintype "passive"))
      (node (ref "R10") (pin "1") (pinfunction "1_1") (pintype "passive"))
      (node (ref "R11") (pin "1") (pinfunction "1_1") (pintype "passive"))
      (node (ref "R14") (pin "1") (pinfunction "1_1") (pintype "passive"))
      (node (ref "R2") (pin "1") (pinfunction "1_1") (pintype "passive"))
      (node (ref "R23") (pin "1") (pinfunction "1_1") (pintype "passive"))
      (node (ref "R24") (pin "1") (pinfunction "1_1") (pintype "passive"))
      (node (ref "R25") (pin "1") (pinfunction "1_1") (pintype "passive"))
      (node (ref "R29") (pin "2") (pinfunction "2_2") (pintype "passive"))
      (node (ref "R3") (pin "1") (pinfunction "1_1") (pintype "passive"))
      (node (ref "R32") (pin "2") (pinfunction "2_2") (pintype "passive"))
      (node (ref "R34") (pin "1") (pinfunction "1_1") (pintype "passive"))
      (node (ref "R35") (pin "1") (pinfunction "1_1") (pintype "passive"))
      (node (ref "R4") (pin "1") (pinfunction "1_1") (pintype "passive"))
      (node (ref "R41") (pin "1") (pinfunction "1_1") (pintype "passive"))
      (node (ref "U4") (pin "2") (pinfunction "+_2") (pintype "passive"))
      (node (ref "U7") (pin "2") (pinfunction "3V3_2") (pintype "passive"))
    )
    (net (code "26") (name "5VCC") (class "Default")
      (node (ref "C2") (pin "2") (pinfunction "2_2") (pintype "passive"))
      (node (ref "C21") (pin "2") (pinfunction "2_2") (pintype "passive"))
      (node (ref "C4") (pin "1") (pinfunction "1_1") (pintype "passive"))
      (node (ref "C5") (pin "1") (pinfunction "1_1") (pintype "passive"))
      (node (ref "C9") (pin "1") (pinfunction "1_1") (pintype "passive"))
      (node (ref "L1") (pin "1") (pinfunction "1_1") (pintype "passive"))
      (node (ref "P2") (pin "1") (pinfunction "1_1") (pintype "passive"))
      (node (ref "P3") (pin "6") (pinfunction "6_6") (pintype "passive"))
      (node (ref "P4") (pin "2") (pinfunction "2_2") (pintype "passive"))
      (node (ref "U10") (pin "8") (pinfunction "VCC_8") (pintype "power_in"))
      (node (ref "U2") (pin "3") (pinfunction "INPUT_3") (pintype "passive"))
      (node (ref "U5") (pin "3") (pinfunction "INPUT_3") (pintype "passive"))
    )
    (net (code "27") (name "5VCC_D") (class "Default")
      (node (ref "B1") (pin "8") (pinfunction "V+_8") (pintype "passive"))
      (node (ref "B2") (pin "8") (pinfunction "V+_8") (pintype "passive"))
      (node (ref "C26") (pin "1") (pinfunction "1_1") (pintype "passive"))
      (node (ref "C27") (pin "1") (pinfunction "1_1") (pintype "passive"))
      (node (ref "C28") (pin "1") (pinfunction "1_1") (pintype "passive"))
      (node (ref "C29") (pin "1") (pinfunction "1_1") (pintype "passive"))
      (node (ref "C8") (pin "2") (pinfunction "2_2") (pintype "passive"))
      (node (ref "L1") (pin "2") (pinfunction "2_2") (pintype "passive"))
      (node (ref "R16") (pin "1") (pinfunction "1_1") (pintype "passive"))
      (node (ref "R38") (pin "1") (pinfunction "1_1") (pintype "passive"))
      (node (ref "U1") (pin "7") (pinfunction "V+_7") (pintype "power_in"))
      (node (ref "U9") (pin "7") (pinfunction "V+_7") (pintype "power_in"))
    )
    (net (code "28") (name "GND_POWER") (class "Default")
      (node (ref "B1") (pin "4") (pinfunction "V-_4") (pintype "passive"))
      (node (ref "B2") (pin "4") (pinfunction "V-_4") (pintype "passive"))
      (node (ref "BT1") (pin "2") (pinfunction "-_2") (pintype "passive"))
      (node (ref "C1") (pin "1") (pinfunction "1_1") (pintype "passive"))
      (node (ref "C11") (pin "2") (pinfunction "2_2") (pintype "passive"))
      (node (ref "C13") (pin "2") (pinfunction "2_2") (pintype "passive"))
      (node (ref "C14") (pin "1") (pinfunction "1_1") (pintype "passive"))
      (node (ref "C15") (pin "1") (pinfunction "1_1") (pintype "passive"))
      (node (ref "C16") (pin "1") (pinfunction "1_1") (pintype "passive"))
      (node (ref "C17") (pin "1") (pinfunction "1_1") (pintype "passive"))
      (node (ref "C18") (pin "2") (pinfunction "2_2") (pintype "passive"))
      (node (ref "C19") (pin "1") (pinfunction "1_1") (pintype "passive"))
      (node (ref "C2") (pin "1") (pinfunction "1_1") (pintype "passive"))
      (node (ref "C20") (pin "1") (pinfunction "1_1") (pintype "passive"))
      (node (ref "C21") (pin "1") (pinfunction "1_1") (pintype "passive"))
      (node (ref "C23") (pin "1") (pinfunction "1_1") (pintype "passive"))
      (node (ref "C24") (pin "1") (pinfunction "1_1") (pintype "passive"))
      (node (ref "C26") (pin "2") (pinfunction "2_2") (pintype "passive"))
      (node (ref "C27") (pin "2") (pinfunction "2_2") (pintype "passive"))
      (node (ref "C28") (pin "2") (pinfunction "2_2") (pintype "passive"))
      (node (ref "C29") (pin "2") (pinfunction "2_2") (pintype "passive"))
      (node (ref "C3") (pin "1") (pinfunction "1_1") (pintype "passive"))
      (node (ref "C4") (pin "2") (pinfunction "2_2") (pintype "passive"))
      (node (ref "C5") (pin "2") (pinfunction "2_2") (pintype "passive"))
      (node (ref "C8") (pin "1") (pinfunction "1_1") (pintype "passive"))
      (node (ref "C9") (pin "2") (pinfunction "2_2") (pintype "passive"))
      (node (ref "FB2") (pin "2") (pinfunction "2_2") (pintype "passive"))
      (node (ref "P1") (pin "1") (pinfunction "1_1") (pintype "passive"))
      (node (ref "P2") (pin "2") (pinfunction "2_2") (pintype "passive"))
      (node (ref "P3") (pin "5") (pinfunction "5_5") (pintype "passive"))
      (node (ref "P4") (pin "3") (pinfunction "3_3") (pintype "passive"))
      (node (ref "R1") (pin "2") (pinfunction "2_2") (pintype "passive"))
      (node (ref "R12") (pin "2") (pinfunction "2_2") (pintype "passive"))
      (node (ref "R18") (pin "2") (pinfunction "2_2") (pintype "passive"))
      (node (ref "R22") (pin "2") (pinfunction "2_2") (pintype "passive"))
      (node (ref "R27") (pin "1") (pinfunction "1_1") (pintype "passive"))
      (node (ref "R37") (pin "2") (pinfunction "2_2") (pintype "passive"))
      (node (ref "R8") (pin "2") (pinfunction "2_2") (pintype "passive"))
      (node (ref "S1") (pin "2") (pinfunction "2_2") (pintype "passive"))
      (node (ref "S2") (pin "4") (pinfunction "NO2_4") (pintype "passive"))
      (node (ref "S3") (pin "2") (pinfunction "2_2") (pintype "passive"))
      (node (ref "U1") (pin "4") (pinfunction "V-_4") (pintype "power_in"))
      (node (ref "U10") (pin "4") (pinfunction "GND_4") (pintype "power_in"))
      (node (ref "U2") (pin "1") (pinfunction "ADJ/GND_1") (pintype "passive"))
      (node (ref "U3") (pin "6") (pinfunction "A2_6") (pintype "passive"))
      (node (ref "U3") (pin "7") (pinfunction "A3_7") (pintype "passive"))
      (node (ref "U5") (pin "1") (pinfunction "ADJ/GND_1") (pintype "passive"))
      (node (ref "U7") (pin "15") (pinfunction "GND2_15") (pintype "passive"))
      (node (ref "U7") (pin "38") (pinfunction "GND_38") (pintype "passive"))
      (node (ref "U7") (pin "39") (pinfunction "P_GND_39") (pintype "passive"))
      (node (ref "U8") (pin "2") (pinfunction "VSS_2") (pintype "passive"))
      (node (ref "U8") (pin "4") (pinfunction "N/A_4") (pintype "passive"))
      (node (ref "U8") (pin "7") (pinfunction "EP_7") (pintype "passive"))
      (node (ref "U9") (pin "4") (pinfunction "V-_4") (pintype "power_in"))
    )
    (net (code "29") (name "Net-(B1-+IN_A)") (class "Default")
      (node (ref "B1") (pin "3") (pinfunction "+IN_A_3") (pintype "passive"))
      (node (ref "R22") (pin "1") (pinfunction "1_1") (pintype "passive"))
    )
    (net (code "30") (name "Net-(B1--IN_A)") (class "Default")
      (node (ref "B1") (pin "2") (pinfunction "-IN_A_2") (pintype "passive"))
      (node (ref "R36") (pin "1") (pinfunction "1_1") (pintype "passive"))
    )
    (net (code "31") (name "Net-(B2-+IN_A)") (class "Default")
      (node (ref "B2") (pin "3") (pinfunction "+IN_A_3") (pintype "passive"))
      (node (ref "R37") (pin "1") (pinfunction "1_1") (pintype "passive"))
    )
    (net (code "32") (name "Net-(B2--IN_A)") (class "Default")
      (node (ref "B2") (pin "2") (pinfunction "-IN_A_2") (pintype "passive"))
      (node (ref "C25") (pin "1") (pinfunction "1_1") (pintype "passive"))
      (node (ref "R39") (pin "1") (pinfunction "1_1") (pintype "passive"))
      (node (ref "R40") (pin "2") (pinfunction "2_2") (pintype "passive"))
    )
    (net (code "33") (name "Net-(B2-OUT_A)") (class "Default")
      (node (ref "B2") (pin "1") (pinfunction "OUT_A_1") (pintype "passive"))
      (node (ref "C25") (pin "2") (pinfunction "2_2") (pintype "passive"))
      (node (ref "R40") (pin "1") (pinfunction "1_1") (pintype "passive"))
      (node (ref "R9") (pin "2") (pinfunction "2_2") (pintype "passive"))
    )
    (net (code "34") (name "Net-(BT1-+)") (class "Default")
      (node (ref "BT1") (pin "1") (pinfunction "+_1") (pintype "passive"))
      (node (ref "U10") (pin "3") (pinfunction "VBAT_3") (pintype "passive"))
    )
    (net (code "35") (name "Net-(C3-Pad2)") (class "Default")
      (node (ref "C3") (pin "2") (pinfunction "2_2") (pintype "passive"))
      (node (ref "R11") (pin "2") (pinfunction "2_2") (pintype "passive"))
      (node (ref "U2") (pin "2") (pinfunction "OUTPUT_2") (pintype "passive"))
      (node (ref "U2") (pin "4") (pinfunction "OUTPUT_4") (pintype "passive"))
    )
    (net (code "36") (name "Net-(C6-Pad2)") (class "Default")
      (node (ref "C6") (pin "2") (pinfunction "2_2") (pintype "passive"))
      (node (ref "C7") (pin "2") (pinfunction "2_2") (pintype "passive"))
      (node (ref "FB2") (pin "1") (pinfunction "1_1") (pintype "passive"))
    )
    (net (code "37") (name "Net-(C10-Pad1)") (class "Default")
      (node (ref "C10") (pin "1") (pinfunction "1_1") (pintype "passive"))
      (node (ref "R5") (pin "1") (pinfunction "1_1") (pintype "passive"))
      (node (ref "R6") (pin "2") (pinfunction "2_2") (pintype "passive"))
    )
    (net (code "38") (name "Net-(C11-Pad1)") (class "Default")
      (node (ref "C11") (pin "1") (pinfunction "1_1") (pintype "passive"))
      (node (ref "R19") (pin "2") (pinfunction "2_2") (pintype "passive"))
      (node (ref "U5") (pin "2") (pinfunction "OUTPUT_2") (pintype "passive"))
      (node (ref "U5") (pin "4") (pinfunction "OUTPUT_4") (pintype "passive"))
    )
    (net (code "39") (name "Net-(C22-Pad1)") (class "Default")
      (node (ref "C22") (pin "1") (pinfunction "1_1") (pintype "passive"))
      (node (ref "R33") (pin "1") (pinfunction "1_1") (pintype "passive"))
      (node (ref "R36") (pin "2") (pinfunction "2_2") (pintype "passive"))
    )
    (net (code "40") (name "Net-(Q1-G)") (class "Default")
      (node (ref "Q1") (pin "3") (pinfunction "G_3") (pintype "passive"))
      (node (ref "R16") (pin "2") (pinfunction "2_2") (pintype "passive"))
    )
    (net (code "41") (name "Net-(Q2-G)") (class "Default")
      (node (ref "Q2") (pin "3") (pinfunction "G_3") (pintype "passive"))
      (node (ref "R38") (pin "2") (pinfunction "2_2") (pintype "passive"))
    )
    (net (code "42") (name "Net-(S2-COMMON2)") (class "Default")
      (node (ref "C20") (pin "2") (pinfunction "2_2") (pintype "passive"))
      (node (ref "R31") (pin "1") (pinfunction "1_1") (pintype "passive"))
      (node (ref "S2") (pin "2") (pinfunction "COMMON2_2") (pintype "passive"))
    )
    (net (code "43") (name "Net-(U1-+IN)") (class "Default")
      (node (ref "R1") (pin "1") (pinfunction "1_1") (pintype "passive"))
      (node (ref "U1") (pin "3") (pinfunction "+IN_3") (pintype "input"))
    )
    (net (code "44") (name "Net-(U1--IN)") (class "Default")
      (node (ref "R6") (pin "1") (pinfunction "1_1") (pintype "passive"))
      (node (ref "U1") (pin "2") (pinfunction "-IN_2") (pintype "input"))
    )
    (net (code "45") (name "Net-(U3-A0)") (class "Default")
      (node (ref "R12") (pin "1") (pinfunction "1_1") (pintype "passive"))
      (node (ref "R7") (pin "2") (pinfunction "2_2") (pintype "passive"))
      (node (ref "U3") (pin "3") (pinfunction "GND_3") (pintype "passive"))
      (node (ref "U3") (pin "4") (pinfunction "A0_4") (pintype "passive"))
    )
    (net (code "46") (name "Net-(U3-ADDR)") (class "Default")
      (node (ref "R7") (pin "1") (pinfunction "1_1") (pintype "passive"))
      (node (ref "U3") (pin "1") (pinfunction "ADDR_1") (pintype "passive"))
    )
    (net (code "47") (name "Net-(U3-ALERT)") (class "Default")
      (node (ref "R2") (pin "2") (pinfunction "2_2") (pintype "passive"))
      (node (ref "U3") (pin "2") (pinfunction "ALERT_2") (pintype "passive"))
    )
    (net (code "48") (name "Net-(U3-VDD)") (class "Default")
      (node (ref "C6") (pin "1") (pinfunction "1_1") (pintype "passive"))
      (node (ref "C7") (pin "1") (pinfunction "1_1") (pintype "passive"))
      (node (ref "FB1") (pin "1") (pinfunction "1_1") (pintype "passive"))
      (node (ref "U3") (pin "8") (pinfunction "VDD_8") (pintype "passive"))
    )
    (net (code "49") (name "Net-(U4-B)") (class "Default")
      (node (ref "R17") (pin "2") (pinfunction "2_2") (pintype "passive"))
      (node (ref "U4") (pin "3") (pinfunction "B_3") (pintype "passive"))
    )
    (net (code "50") (name "Net-(U4-G)") (class "Default")
      (node (ref "R15") (pin "2") (pinfunction "2_2") (pintype "passive"))
      (node (ref "U4") (pin "4") (pinfunction "G_4") (pintype "passive"))
    )
    (net (code "51") (name "Net-(U4-R)") (class "Default")
      (node (ref "R13") (pin "2") (pinfunction "2_2") (pintype "passive"))
      (node (ref "U4") (pin "1") (pinfunction "R_1") (pintype "passive"))
    )
    (net (code "52") (name "Net-(U7-IO2)") (class "Default")
      (node (ref "R27") (pin "2") (pinfunction "2_2") (pintype "passive"))
      (node (ref "U7") (pin "24") (pinfunction "IO2_24") (pintype "passive"))
    )
    (net (code "53") (name "Net-(U8-VDD)") (class "Default")
      (node (ref "C18") (pin "1") (pinfunction "1_1") (pintype "passive"))
      (node (ref "R28") (pin "1") (pinfunction "1_1") (pintype "passive"))
      (node (ref "U8") (pin "1") (pinfunction "VDD_1") (pintype "passive"))
    )
    (net (code "54") (name "Net-(U9-+IN)") (class "Default")
      (node (ref "R8") (pin "1") (pinfunction "1_1") (pintype "passive"))
      (node (ref "U9") (pin "3") (pinfunction "+IN_3") (pintype "input"))
    )
    (net (code "55") (name "Net-(U9--IN)") (class "Default")
      (node (ref "C12") (pin "1") (pinfunction "1_1") (pintype "passive"))
      (node (ref "R20") (pin "1") (pinfunction "1_1") (pintype "passive"))
      (node (ref "R21") (pin "2") (pinfunction "2_2") (pintype "passive"))
      (node (ref "U9") (pin "2") (pinfunction "-IN_2") (pintype "input"))
    )
    (net (code "56") (name "Net-(U10-X1)") (class "Default")
      (node (ref "C23") (pin "2") (pinfunction "2_2") (pintype "passive"))
      (node (ref "U10") (pin "1") (pinfunction "X1_1") (pintype "passive"))
      (node (ref "X1") (pin "1") (pinfunction "inp_1") (pintype "passive"))
    )
    (net (code "57") (name "Net-(U10-X2)") (class "Default")
      (node (ref "C24") (pin "2") (pinfunction "2_2") (pintype "passive"))
      (node (ref "U10") (pin "2") (pinfunction "X2_2") (pintype "passive"))
      (node (ref "X1") (pin "2") (pinfunction "out_2") (pintype "passive"))
    )
    (net (code "58") (name "unconnected-(B1-+IN_B-Pad5)") (class "Default")
      (node (ref "B1") (pin "5") (pinfunction "+IN_B_5") (pintype "passive+no_connect"))
    )
    (net (code "59") (name "unconnected-(B1--IN_B-Pad6)") (class "Default")
      (node (ref "B1") (pin "6") (pinfunction "-IN_B_6") (pintype "passive+no_connect"))
    )
    (net (code "60") (name "unconnected-(B1-OUT_B-Pad7)") (class "Default")
      (node (ref "B1") (pin "7") (pinfunction "OUT_B_7") (pintype "passive+no_connect"))
    )
    (net (code "61") (name "unconnected-(B2-+IN_B-Pad5)") (class "Default")
      (node (ref "B2") (pin "5") (pinfunction "+IN_B_5") (pintype "passive+no_connect"))
    )
    (net (code "62") (name "unconnected-(B2--IN_B-Pad6)") (class "Default")
      (node (ref "B2") (pin "6") (pinfunction "-IN_B_6") (pintype "passive+no_connect"))
    )
    (net (code "63") (name "unconnected-(B2-OUT_B-Pad7)") (class "Default")
      (node (ref "B2") (pin "7") (pinfunction "OUT_B_7") (pintype "passive+no_connect"))
    )
    (net (code "64") (name "unconnected-(S2-COMMON1-Pad1)") (class "Default")
      (node (ref "S2") (pin "1") (pinfunction "COMMON1_1") (pintype "passive+no_connect"))
    )
    (net (code "65") (name "unconnected-(S2-NO1-Pad3)") (class "Default")
      (node (ref "S2") (pin "3") (pinfunction "NO1_3") (pintype "passive+no_connect"))
    )
    (net (code "66") (name "unconnected-(U7-CLK-Pad20)") (class "Default")
      (node (ref "U7") (pin "20") (pinfunction "CLK_20") (pintype "passive+no_connect"))
    )
    (net (code "67") (name "unconnected-(U7-CMD-Pad19)") (class "Default")
      (node (ref "U7") (pin "19") (pinfunction "CMD_19") (pintype "passive+no_connect"))
    )
    (net (code "68") (name "unconnected-(U7-IO4-Pad26)") (class "Default")
      (node (ref "U7") (pin "26") (pinfunction "IO4_26") (pintype "passive+no_connect"))
    )
    (net (code "69") (name "unconnected-(U7-IO5-Pad29)") (class "Default")
      (node (ref "U7") (pin "29") (pinfunction "IO5_29") (pintype "passive+no_connect"))
    )
    (net (code "70") (name "unconnected-(U7-IO12-Pad14)") (class "Default")
      (node (ref "U7") (pin "14") (pinfunction "IO12_14") (pintype "passive+no_connect"))
    )
    (net (code "71") (name "unconnected-(U7-IO13-Pad16)") (class "Default")
      (node (ref "U7") (pin "16") (pinfunction "IO13_16") (pintype "passive+no_connect"))
    )
    (net (code "72") (name "unconnected-(U7-IO15-Pad23)") (class "Default")
      (node (ref "U7") (pin "23") (pinfunction "IO15_23") (pintype "passive+no_connect"))
    )
    (net (code "73") (name "unconnected-(U7-IO23-Pad37)") (class "Default")
      (node (ref "U7") (pin "37") (pinfunction "IO23_37") (pintype "passive+no_connect"))
    )
    (net (code "74") (name "unconnected-(U7-IO33-Pad9)") (class "Default")
      (node (ref "U7") (pin "9") (pinfunction "IO33_9") (pintype "passive+no_connect"))
    )
    (net (code "75") (name "unconnected-(U7-IO35-Pad7)") (class "Default")
      (node (ref "U7") (pin "7") (pinfunction "IO35_7") (pintype "passive+no_connect"))
    )
    (net (code "76") (name "unconnected-(U7-NC-Pad32)") (class "Default")
      (node (ref "U7") (pin "32") (pinfunction "NC_32") (pintype "passive+no_connect"))
    )
    (net (code "77") (name "unconnected-(U7-SD0-Pad21)") (class "Default")
      (node (ref "U7") (pin "21") (pinfunction "SD0_21") (pintype "passive+no_connect"))
    )
    (net (code "78") (name "unconnected-(U7-SD1-Pad22)") (class "Default")
      (node (ref "U7") (pin "22") (pinfunction "SD1_22") (pintype "passive+no_connect"))
    )
    (net (code "79") (name "unconnected-(U7-SD2-Pad17)") (class "Default")
      (node (ref "U7") (pin "17") (pinfunction "SD2_17") (pintype "passive+no_connect"))
    )
    (net (code "80") (name "unconnected-(U7-SD3-Pad18)") (class "Default")
      (node (ref "U7") (pin "18") (pinfunction "SD3_18") (pintype "passive+no_connect"))
    )
    (net (code "81") (name "unconnected-(U7-SENSOR_VN-Pad5)") (class "Default")
      (node (ref "U7") (pin "5") (pinfunction "SENSOR_VN_5") (pintype "passive+no_connect"))
    )
    (net (code "82") (name "unconnected-(U7-SENSOR_VP-Pad4)") (class "Default")
      (node (ref "U7") (pin "4") (pinfunction "SENSOR_VP_4") (pintype "passive+no_connect"))
    )
    (net (code "83") (name "unconnected-(U10-SQW-Pad7)") (class "Default")
      (node (ref "U10") (pin "7") (pinfunction "SQW_7") (pintype "passive+no_connect"))
    )
  )
)
